# Sheet1.net
KiCad netlist of a schematic drawn in Altium Designer
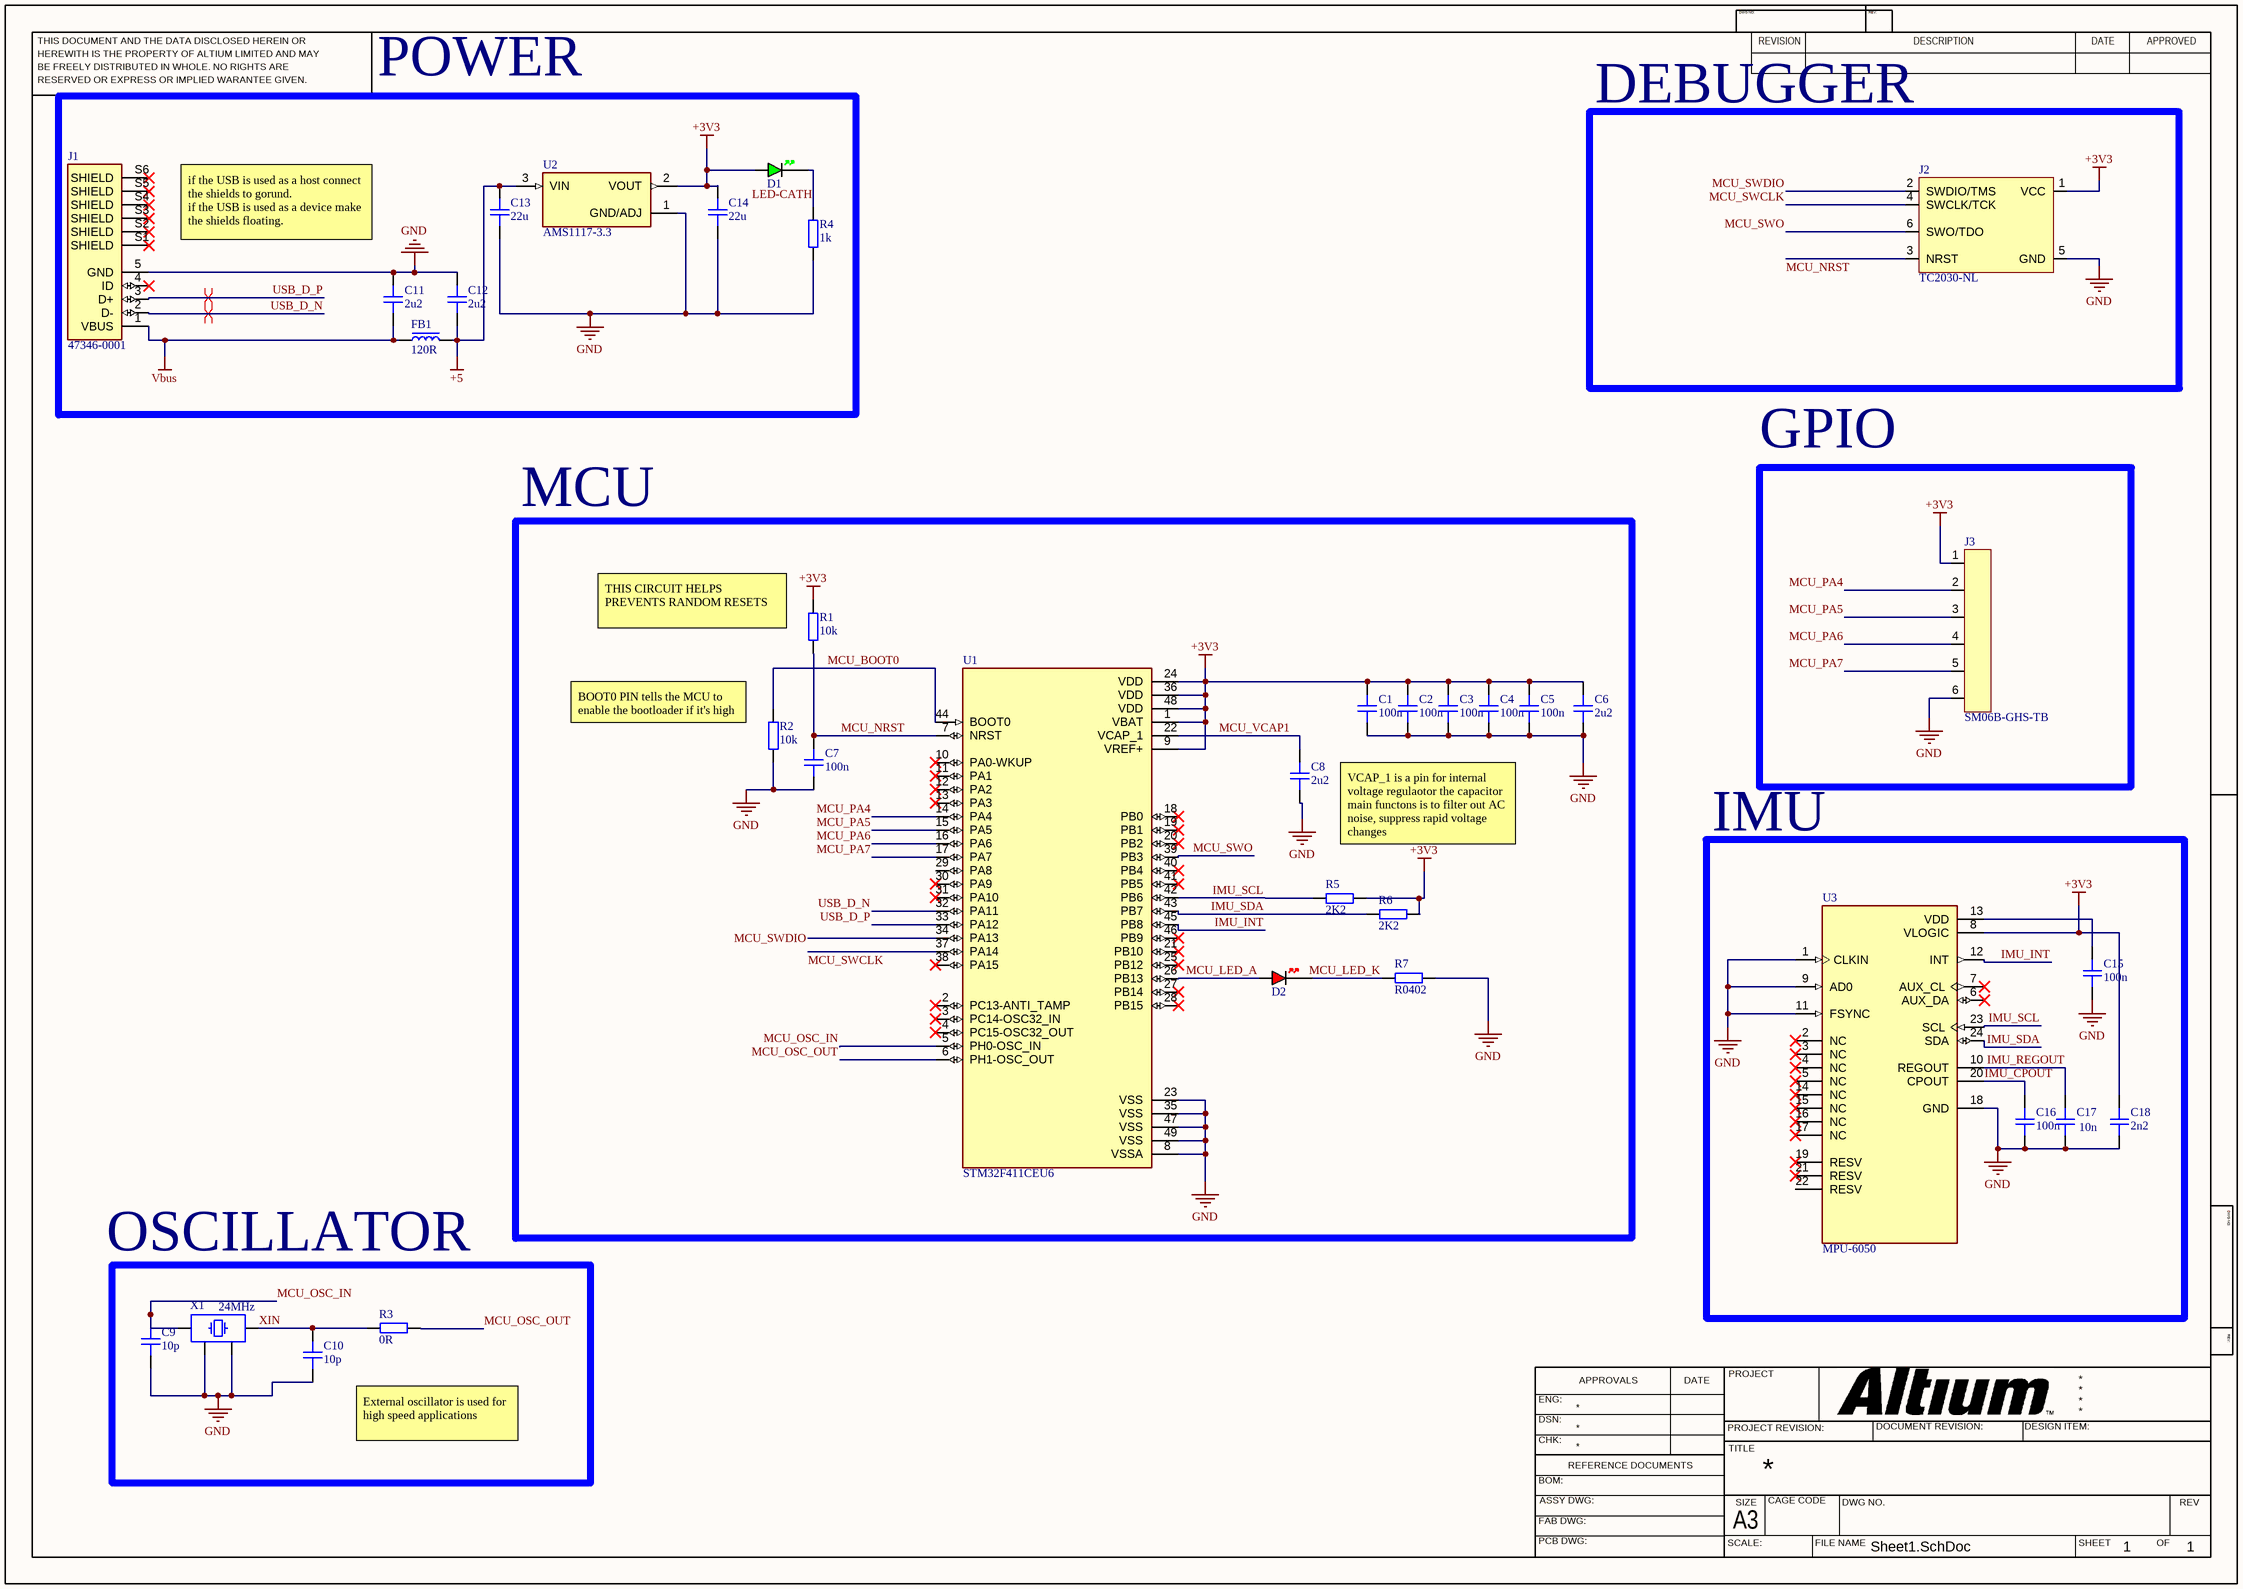
[diagram p0: Sheet1.SchDoc]

(export (version "E")
  (design (tool "Eeschema 10.0.6"))
  (components
    (comp (ref "C1")
      (value "100n")
      (footprint "CAP_0402")
      (description "Capacitor SMD 0402")
      (libsource (lib "Schematic-Lib-PhilsLab") (part "CAP_0402"))
    )
    (comp (ref "C2")
      (value "100n")
      (footprint "CAP_0402")
      (description "Capacitor SMD 0402")
      (libsource (lib "Schematic-Lib-PhilsLab") (part "CAP_0402"))
    )
    (comp (ref "C3")
      (value "100n")
      (footprint "CAP_0402")
      (description "Capacitor SMD 0402")
      (libsource (lib "Schematic-Lib-PhilsLab") (part "CAP_0402"))
    )
    (comp (ref "C4")
      (value "100n")
      (footprint "CAP_0402")
      (description "Capacitor SMD 0402")
      (libsource (lib "Schematic-Lib-PhilsLab") (part "CAP_0402"))
    )
    (comp (ref "C5")
      (value "100n")
      (footprint "CAP_0402")
      (description "Capacitor SMD 0402")
      (libsource (lib "Schematic-Lib-PhilsLab") (part "CAP_0402"))
    )
    (comp (ref "C6")
      (value "2u2")
      (footprint "CAP_0402")
      (description "Capacitor SMD 0402")
      (libsource (lib "Schematic-Lib-PhilsLab") (part "CAP_0402"))
    )
    (comp (ref "C7")
      (value "100n")
      (footprint "CAP_0402")
      (description "Capacitor SMD 0402")
      (libsource (lib "Schematic-Lib-PhilsLab") (part "CAP_0402"))
    )
    (comp (ref "C8")
      (value "2u2")
      (footprint "CAP_0402")
      (description "Capacitor SMD 0402")
      (libsource (lib "Schematic-Lib-PhilsLab") (part "CAP_0402"))
    )
    (comp (ref "C9")
      (value "10p")
      (footprint "CAP_0402")
      (description "Capacitor SMD 0402")
      (libsource (lib "Schematic-Lib-PhilsLab") (part "CAP_0402"))
    )
    (comp (ref "C10")
      (value "10p")
      (footprint "CAP_0402")
      (description "Capacitor SMD 0402")
      (libsource (lib "Schematic-Lib-PhilsLab") (part "CAP_0402"))
    )
    (comp (ref "C11")
      (value "2u2")
      (footprint "CAP_0402")
      (description "Capacitor SMD 0402")
      (libsource (lib "Schematic-Lib-PhilsLab") (part "CAP_0402"))
    )
    (comp (ref "C12")
      (value "2u2")
      (footprint "CAP_0402")
      (description "Capacitor SMD 0402")
      (libsource (lib "Schematic-Lib-PhilsLab") (part "CAP_0402"))
    )
    (comp (ref "C13")
      (value "22u")
      (footprint "CAP_0402")
      (description "Capacitor SMD 0402")
      (libsource (lib "Schematic-Lib-PhilsLab") (part "CAP_0402"))
    )
    (comp (ref "C14")
      (value "22u")
      (footprint "CAP_0402")
      (description "Capacitor SMD 0402")
      (libsource (lib "Schematic-Lib-PhilsLab") (part "CAP_0402"))
    )
    (comp (ref "C15")
      (value "100n")
      (footprint "CAP_0402")
      (description "Capacitor SMD 0402")
      (libsource (lib "Schematic-Lib-PhilsLab") (part "CAP_0402"))
    )
    (comp (ref "C16")
      (value "100n")
      (footprint "CAP_0402")
      (description "Capacitor SMD 0402")
      (libsource (lib "Schematic-Lib-PhilsLab") (part "CAP_0402"))
    )
    (comp (ref "C17")
      (value "10n")
      (footprint "CAP_0402")
      (description "Capacitor SMD 0402")
      (libsource (lib "Schematic-Lib-PhilsLab") (part "CAP_0402"))
    )
    (comp (ref "C18")
      (value "2n2")
      (footprint "CAP_0402")
      (description "Capacitor SMD 0402")
      (libsource (lib "Schematic-Lib-PhilsLab") (part "CAP_0402"))
    )
    (comp (ref "D1")
      (value "GREEN")
      (footprint "LED_0402_GREEN")
      (description "LED 0402 GREEN SMD")
      (libsource (lib "Schematic-Lib-PhilsLab") (part "LED_0402_GREEN"))
    )
    (comp (ref "D2")
      (value "RED")
      (footprint "LED_0402_RED")
      (description "LED 0402 RED SMD")
      (libsource (lib "Schematic-Lib-PhilsLab") (part "LED_0402_RED"))
    )
    (comp (ref "FB1")
      (value "120R")
      (footprint "FB_0805")
      (description "Ferrite Bead SMD 0805")
      (libsource (lib "Schematic-Lib-PhilsLab") (part "FB_0805"))
    )
    (comp (ref "J1")
      (value "47346-0001")
      (footprint "MOLEX_47346-0001")
      (description "Conn Data USB Micro B w/Flange SMT Bottom Mnt LF ¦ Molex Incorporated 47346-0001")
      (fields (field (name "MF") "Molex"))
      (libsource (lib "47346-0001") (part "47346-0001"))
    )
    (comp (ref "J2")
      (value "TC2030-NL")
      (footprint "TC2030-NL-FP")
      (description "Tag-Connect No-Solder SWD Debug Connector (No Legs) DO NOT PLACE")
      (fields
        (field (name "MANUFACTURER") "Tag-Connect")
        (field (name "MANUFACTURER PART NUMBER") "TC2030-NL-FP")
      )
      (libsource (lib "Schematic-Lib-PhilsLab") (part "TC2030-NL"))
    )
    (comp (ref "J3")
      (value "SM06B-GHS-TB")
      (footprint "SM06B-GHS-TB")
      (description "Header Connector 6 Position 1.25MM Pitch SMD Horizontal JST GH")
      (fields (field (name "MANUFACTURER") "JST"))
      (libsource (lib "Schematic-Lib-PhilsLab") (part "SM06B-GHS-TB"))
    )
    (comp (ref "R1")
      (value "10k")
      (footprint "RES_0402")
      (description "Resistor SMD 0402")
      (libsource (lib "Schematic-Lib-PhilsLab") (part "RES_0402"))
    )
    (comp (ref "R2")
      (value "10k")
      (footprint "RES_0402")
      (description "Resistor SMD 0402")
      (libsource (lib "Schematic-Lib-PhilsLab") (part "RES_0402"))
    )
    (comp (ref "R3")
      (value "0R")
      (footprint "RES_0402")
      (description "Resistor SMD 0402")
      (libsource (lib "Schematic-Lib-PhilsLab") (part "RES_0402"))
    )
    (comp (ref "R4")
      (value "1k")
      (footprint "RES_0402")
      (description "Resistor SMD 0402")
      (libsource (lib "Schematic-Lib-PhilsLab") (part "RES_0402"))
    )
    (comp (ref "R5")
      (value "2K2")
      (footprint "RES_0402")
      (description "Resistor SMD 0402")
      (libsource (lib "Schematic-Lib-PhilsLab") (part "RES_0402"))
    )
    (comp (ref "R6")
      (value "2K2")
      (footprint "RES_0402")
      (description "Resistor SMD 0402")
      (libsource (lib "Schematic-Lib-PhilsLab") (part "RES_0402"))
    )
    (comp (ref "R7")
      (value "R0402")
      (footprint "RES_0402")
      (description "Resistor SMD 0402")
      (libsource (lib "Schematic-Lib-PhilsLab") (part "RES_0402"))
    )
    (comp (ref "U1")
      (value "STM32F411CEU6")
      (footprint "QFN50P700X700X60-49N")
      (libsource (lib "STM32F411CEU6") (part "STM32F411CEU6"))
    )
    (comp (ref "U2")
      (value "AMS1117-3.3")
      (footprint "SOT229P700X180-4N")
      (description "Sot223/Pkg 1-Amp 3.3-Volt Low Drop Out Voltage Regulatator")
      (fields (field (name "MF") "Advanced Monolithic Systems"))
      (libsource (lib "AMS1117-3.3") (part "AMS1117-3.3"))
    )
    (comp (ref "U3")
      (value "MPU-6050")
      (footprint "QFN50P400X400X95-24N")
      (description "MPU-6050 series Accelerometer, Gyroscope, 3 Axis Sensor Evaluation Board")
      (fields (field (name "MF") "TDK InvenSense"))
      (libsource (lib "MPU-6050") (part "MPU-6050"))
    )
    (comp (ref "X1")
      (value "24MHz")
      (footprint "XTAL_3225")
      (description "Crystal SMD 24MHz 10PPM 7pF 3225")
      (fields
        (field (name "MANUFACTURER") "Epson")
        (field (name "MANUFACTURER PART NUMBER") "TSX-3225 24.0000MF15X-AC")
      )
      (libsource (lib "Schematic-Lib-PhilsLab") (part "TSX-3225_24.0000MF15X-AC"))
    )
  )
  (nets
    (net (code "1") (name "+3V3") (class "Default")
      (node (ref "C1") (pin "2") (pinfunction "2_2") (pintype "passive"))
      (node (ref "C14") (pin "2") (pinfunction "2_2") (pintype "passive"))
      (node (ref "C18") (pin "2") (pinfunction "2_2") (pintype "passive"))
      (node (ref "C2") (pin "2") (pinfunction "2_2") (pintype "passive"))
      (node (ref "C3") (pin "2") (pinfunction "2_2") (pintype "passive"))
      (node (ref "C4") (pin "2") (pinfunction "2_2") (pintype "passive"))
      (node (ref "C5") (pin "2") (pinfunction "2_2") (pintype "passive"))
      (node (ref "C6") (pin "2") (pinfunction "2_2") (pintype "passive"))
      (node (ref "D1") (pin "A") (pinfunction "A_A") (pintype "passive"))
      (node (ref "J2") (pin "1") (pinfunction "VCC_1") (pintype "passive"))
      (node (ref "J3") (pin "1") (pinfunction "1_1") (pintype "passive"))
      (node (ref "R1") (pin "2") (pinfunction "2_2") (pintype "passive"))
      (node (ref "R5") (pin "2") (pinfunction "2_2") (pintype "passive"))
      (node (ref "R6") (pin "2") (pinfunction "2_2") (pintype "passive"))
      (node (ref "U1") (pin "1") (pinfunction "VBAT_1") (pintype "power_in"))
      (node (ref "U1") (pin "24") (pinfunction "VDD_24") (pintype "power_in"))
      (node (ref "U1") (pin "36") (pinfunction "VDD_36") (pintype "power_in"))
      (node (ref "U1") (pin "48") (pinfunction "VDD_48") (pintype "power_in"))
      (node (ref "U1") (pin "9") (pinfunction "VREF+_9") (pintype "power_in"))
      (node (ref "U2") (pin "2") (pinfunction "VOUT_2") (pintype "output"))
      (node (ref "U3") (pin "8") (pinfunction "VLOGIC_8") (pintype "power_in"))
    )
    (net (code "2") (name "+5") (class "Default")
      (node (ref "C12") (pin "1") (pinfunction "1_1") (pintype "passive"))
      (node (ref "C13") (pin "2") (pinfunction "2_2") (pintype "passive"))
      (node (ref "FB1") (pin "2") (pinfunction "2_2") (pintype "passive"))
      (node (ref "U2") (pin "3") (pinfunction "VIN_3") (pintype "input"))
    )
    (net (code "3") (name "/IMU_CPOUT") (class "Default")
      (node (ref "C16") (pin "2") (pinfunction "2_2") (pintype "passive"))
      (node (ref "U3") (pin "20") (pinfunction "CPOUT_20") (pintype "passive"))
    )
    (net (code "4") (name "/IMU_INT") (class "Default")
      (node (ref "U1") (pin "45") (pinfunction "PB8_45") (pintype "bidirectional"))
      (node (ref "U3") (pin "12") (pinfunction "INT_12") (pintype "output"))
    )
    (net (code "5") (name "/IMU_REGOUT") (class "Default")
      (node (ref "C17") (pin "2") (pinfunction "2_2") (pintype "passive"))
      (node (ref "U3") (pin "10") (pinfunction "REGOUT_10") (pintype "passive"))
    )
    (net (code "6") (name "/IMU_SCL") (class "Default")
      (node (ref "R5") (pin "1") (pinfunction "1_1") (pintype "passive"))
      (node (ref "U1") (pin "42") (pinfunction "PB6_42") (pintype "bidirectional"))
      (node (ref "U3") (pin "23") (pinfunction "SCL_23") (pintype "input"))
    )
    (net (code "7") (name "/IMU_SDA") (class "Default")
      (node (ref "R6") (pin "1") (pinfunction "1_1") (pintype "passive"))
      (node (ref "U1") (pin "43") (pinfunction "PB7_43") (pintype "bidirectional"))
      (node (ref "U3") (pin "24") (pinfunction "SDA_24") (pintype "bidirectional"))
    )
    (net (code "8") (name "/LED-CATH") (class "Default")
      (node (ref "D1") (pin "K") (pinfunction "K_K") (pintype "passive"))
      (node (ref "R4") (pin "2") (pinfunction "2_2") (pintype "passive"))
    )
    (net (code "9") (name "/MCU_BOOT0") (class "Default")
      (node (ref "R2") (pin "2") (pinfunction "2_2") (pintype "passive"))
      (node (ref "U1") (pin "44") (pinfunction "BOOT0_44") (pintype "input"))
    )
    (net (code "10") (name "/MCU_LED_A") (class "Default")
      (node (ref "D2") (pin "A") (pinfunction "A_A") (pintype "passive"))
      (node (ref "U1") (pin "26") (pinfunction "PB13_26") (pintype "bidirectional"))
    )
    (net (code "11") (name "/MCU_LED_K") (class "Default")
      (node (ref "D2") (pin "K") (pinfunction "K_K") (pintype "passive"))
      (node (ref "R7") (pin "1") (pinfunction "1_1") (pintype "passive"))
    )
    (net (code "12") (name "/MCU_NRST") (class "Default")
      (node (ref "C7") (pin "2") (pinfunction "2_2") (pintype "passive"))
      (node (ref "J2") (pin "3") (pinfunction "NRST_3") (pintype "passive"))
      (node (ref "R1") (pin "1") (pinfunction "1_1") (pintype "passive"))
      (node (ref "U1") (pin "7") (pinfunction "NRST_7") (pintype "bidirectional"))
    )
    (net (code "13") (name "/MCU_OSC_IN") (class "Default")
      (node (ref "C9") (pin "2") (pinfunction "2_2") (pintype "passive"))
      (node (ref "U1") (pin "5") (pinfunction "PH0-OSC_IN_5") (pintype "bidirectional"))
      (node (ref "X1") (pin "1") (pinfunction "1_1") (pintype "passive"))
    )
    (net (code "14") (name "/MCU_OSC_OUT") (class "Default")
      (node (ref "R3") (pin "2") (pinfunction "2_2") (pintype "passive"))
      (node (ref "U1") (pin "6") (pinfunction "PH1-OSC_OUT_6") (pintype "bidirectional"))
    )
    (net (code "15") (name "/MCU_PA4") (class "Default")
      (node (ref "J3") (pin "2") (pinfunction "2_2") (pintype "passive"))
      (node (ref "U1") (pin "14") (pinfunction "PA4_14") (pintype "bidirectional"))
    )
    (net (code "16") (name "/MCU_PA5") (class "Default")
      (node (ref "J3") (pin "3") (pinfunction "3_3") (pintype "passive"))
      (node (ref "U1") (pin "15") (pinfunction "PA5_15") (pintype "bidirectional"))
    )
    (net (code "17") (name "/MCU_PA6") (class "Default")
      (node (ref "J3") (pin "4") (pinfunction "4_4") (pintype "passive"))
      (node (ref "U1") (pin "16") (pinfunction "PA6_16") (pintype "bidirectional"))
    )
    (net (code "18") (name "/MCU_PA7") (class "Default")
      (node (ref "J3") (pin "5") (pinfunction "5_5") (pintype "passive"))
      (node (ref "U1") (pin "17") (pinfunction "PA7_17") (pintype "bidirectional"))
    )
    (net (code "19") (name "/MCU_SWCLK") (class "Default")
      (node (ref "J2") (pin "4") (pinfunction "SWCLK/TCK_4") (pintype "passive"))
      (node (ref "U1") (pin "37") (pinfunction "PA14_37") (pintype "bidirectional"))
    )
    (net (code "20") (name "/MCU_SWDIO") (class "Default")
      (node (ref "J2") (pin "2") (pinfunction "SWDIO/TMS_2") (pintype "passive"))
      (node (ref "U1") (pin "34") (pinfunction "PA13_34") (pintype "bidirectional"))
    )
    (net (code "21") (name "/MCU_SWO") (class "Default")
      (node (ref "J2") (pin "6") (pinfunction "SWO/TDO_6") (pintype "passive"))
      (node (ref "U1") (pin "39") (pinfunction "PB3_39") (pintype "bidirectional"))
    )
    (net (code "22") (name "/MCU_VCAP1") (class "Default")
      (node (ref "C8") (pin "2") (pinfunction "2_2") (pintype "passive"))
      (node (ref "U1") (pin "22") (pinfunction "VCAP_1_22") (pintype "power_in"))
    )
    (net (code "23") (name "/USB_D_N") (class "Default")
      (node (ref "J1") (pin "2") (pinfunction "D-_2") (pintype "bidirectional"))
      (node (ref "U1") (pin "32") (pinfunction "PA11_32") (pintype "bidirectional"))
    )
    (net (code "24") (name "/USB_D_P") (class "Default")
      (node (ref "J1") (pin "3") (pinfunction "D+_3") (pintype "bidirectional"))
      (node (ref "U1") (pin "33") (pinfunction "PA12_33") (pintype "bidirectional"))
    )
    (net (code "25") (name "/XIN") (class "Default")
      (node (ref "C10") (pin "2") (pinfunction "2_2") (pintype "passive"))
      (node (ref "R3") (pin "1") (pinfunction "1_1") (pintype "passive"))
      (node (ref "X1") (pin "3") (pinfunction "3_3") (pintype "passive"))
    )
    (net (code "26") (name "GND") (class "Default")
      (node (ref "C1") (pin "1") (pinfunction "1_1") (pintype "passive"))
      (node (ref "C10") (pin "1") (pinfunction "1_1") (pintype "passive"))
      (node (ref "C11") (pin "2") (pinfunction "2_2") (pintype "passive"))
      (node (ref "C12") (pin "2") (pinfunction "2_2") (pintype "passive"))
      (node (ref "C13") (pin "1") (pinfunction "1_1") (pintype "passive"))
      (node (ref "C14") (pin "1") (pinfunction "1_1") (pintype "passive"))
      (node (ref "C15") (pin "1") (pinfunction "1_1") (pintype "passive"))
      (node (ref "C16") (pin "1") (pinfunction "1_1") (pintype "passive"))
      (node (ref "C17") (pin "1") (pinfunction "1_1") (pintype "passive"))
      (node (ref "C18") (pin "1") (pinfunction "1_1") (pintype "passive"))
      (node (ref "C2") (pin "1") (pinfunction "1_1") (pintype "passive"))
      (node (ref "C3") (pin "1") (pinfunction "1_1") (pintype "passive"))
      (node (ref "C4") (pin "1") (pinfunction "1_1") (pintype "passive"))
      (node (ref "C5") (pin "1") (pinfunction "1_1") (pintype "passive"))
      (node (ref "C6") (pin "1") (pinfunction "1_1") (pintype "passive"))
      (node (ref "C7") (pin "1") (pinfunction "1_1") (pintype "passive"))
      (node (ref "C8") (pin "1") (pinfunction "1_1") (pintype "passive"))
      (node (ref "C9") (pin "1") (pinfunction "1_1") (pintype "passive"))
      (node (ref "J1") (pin "5") (pinfunction "GND_5") (pintype "power_in"))
      (node (ref "J2") (pin "5") (pinfunction "GND_5") (pintype "passive"))
      (node (ref "J3") (pin "6") (pinfunction "6_6") (pintype "passive"))
      (node (ref "R2") (pin "1") (pinfunction "1_1") (pintype "passive"))
      (node (ref "R4") (pin "1") (pinfunction "1_1") (pintype "passive"))
      (node (ref "R7") (pin "2") (pinfunction "2_2") (pintype "passive"))
      (node (ref "U1") (pin "23") (pinfunction "VSS_23") (pintype "power_in"))
      (node (ref "U1") (pin "35") (pinfunction "VSS_35") (pintype "power_in"))
      (node (ref "U1") (pin "47") (pinfunction "VSS_47") (pintype "power_in"))
      (node (ref "U1") (pin "49") (pinfunction "VSS_49") (pintype "power_in"))
      (node (ref "U1") (pin "8") (pinfunction "VSSA_8") (pintype "power_in"))
      (node (ref "U2") (pin "1") (pinfunction "GND/ADJ_1") (pintype "power_in"))
      (node (ref "U3") (pin "1") (pinfunction "CLKIN_1") (pintype "input"))
      (node (ref "U3") (pin "11") (pinfunction "FSYNC_11") (pintype "input"))
      (node (ref "U3") (pin "18") (pinfunction "GND_18") (pintype "power_in"))
      (node (ref "U3") (pin "9") (pinfunction "AD0_9") (pintype "input"))
      (node (ref "X1") (pin "2") (pinfunction "2_2") (pintype "passive"))
      (node (ref "X1") (pin "4") (pinfunction "4_4") (pintype "passive"))
    )
    (net (code "27") (name "Net-(U3-VDD)") (class "Default")
      (node (ref "C15") (pin "2") (pinfunction "2_2") (pintype "passive"))
      (node (ref "U3") (pin "13") (pinfunction "VDD_13") (pintype "power_in"))
    )
    (net (code "28") (name "Vbus") (class "Default")
      (node (ref "C11") (pin "1") (pinfunction "1_1") (pintype "passive"))
      (node (ref "FB1") (pin "1") (pinfunction "1_1") (pintype "passive"))
      (node (ref "J1") (pin "1") (pinfunction "VBUS_1") (pintype "power_in"))
    )
    (net (code "29") (name "unconnected-(J1-ID-Pad4)") (class "Default")
      (node (ref "J1") (pin "4") (pinfunction "ID_4") (pintype "bidirectional+no_connect"))
    )
    (net (code "30") (name "unconnected-(J1-SHIELD-PadS1)") (class "Default")
      (node (ref "J1") (pin "S1") (pinfunction "SHIELD_S1") (pintype "passive+no_connect"))
    )
    (net (code "31") (name "unconnected-(J1-SHIELD-PadS2)") (class "Default")
      (node (ref "J1") (pin "S2") (pinfunction "SHIELD_S2") (pintype "passive+no_connect"))
    )
    (net (code "32") (name "unconnected-(J1-SHIELD-PadS3)") (class "Default")
      (node (ref "J1") (pin "S3") (pinfunction "SHIELD_S3") (pintype "passive+no_connect"))
    )
    (net (code "33") (name "unconnected-(J1-SHIELD-PadS4)") (class "Default")
      (node (ref "J1") (pin "S4") (pinfunction "SHIELD_S4") (pintype "passive+no_connect"))
    )
    (net (code "34") (name "unconnected-(J1-SHIELD-PadS5)") (class "Default")
      (node (ref "J1") (pin "S5") (pinfunction "SHIELD_S5") (pintype "passive+no_connect"))
    )
    (net (code "35") (name "unconnected-(J1-SHIELD-PadS6)") (class "Default")
      (node (ref "J1") (pin "S6") (pinfunction "SHIELD_S6") (pintype "passive+no_connect"))
    )
    (net (code "36") (name "unconnected-(U1-PA0-WKUP-Pad10)") (class "Default")
      (node (ref "U1") (pin "10") (pinfunction "PA0-WKUP_10") (pintype "bidirectional+no_connect"))
    )
    (net (code "37") (name "unconnected-(U1-PA1-Pad11)") (class "Default")
      (node (ref "U1") (pin "11") (pinfunction "PA1_11") (pintype "bidirectional+no_connect"))
    )
    (net (code "38") (name "unconnected-(U1-PA2-Pad12)") (class "Default")
      (node (ref "U1") (pin "12") (pinfunction "PA2_12") (pintype "bidirectional+no_connect"))
    )
    (net (code "39") (name "unconnected-(U1-PA3-Pad13)") (class "Default")
      (node (ref "U1") (pin "13") (pinfunction "PA3_13") (pintype "bidirectional+no_connect"))
    )
    (net (code "40") (name "unconnected-(U1-PA8-Pad29)") (class "Default")
      (node (ref "U1") (pin "29") (pinfunction "PA8_29") (pintype "bidirectional"))
    )
    (net (code "41") (name "unconnected-(U1-PA9-Pad30)") (class "Default")
      (node (ref "U1") (pin "30") (pinfunction "PA9_30") (pintype "bidirectional+no_connect"))
    )
    (net (code "42") (name "unconnected-(U1-PA10-Pad31)") (class "Default")
      (node (ref "U1") (pin "31") (pinfunction "PA10_31") (pintype "bidirectional+no_connect"))
    )
    (net (code "43") (name "unconnected-(U1-PA15-Pad38)") (class "Default")
      (node (ref "U1") (pin "38") (pinfunction "PA15_38") (pintype "bidirectional+no_connect"))
    )
    (net (code "44") (name "unconnected-(U1-PB0-Pad18)") (class "Default")
      (node (ref "U1") (pin "18") (pinfunction "PB0_18") (pintype "bidirectional+no_connect"))
    )
    (net (code "45") (name "unconnected-(U1-PB1-Pad19)") (class "Default")
      (node (ref "U1") (pin "19") (pinfunction "PB1_19") (pintype "bidirectional+no_connect"))
    )
    (net (code "46") (name "unconnected-(U1-PB2-Pad20)") (class "Default")
      (node (ref "U1") (pin "20") (pinfunction "PB2_20") (pintype "bidirectional+no_connect"))
    )
    (net (code "47") (name "unconnected-(U1-PB4-Pad40)") (class "Default")
      (node (ref "U1") (pin "40") (pinfunction "PB4_40") (pintype "bidirectional+no_connect"))
    )
    (net (code "48") (name "unconnected-(U1-PB5-Pad41)") (class "Default")
      (node (ref "U1") (pin "41") (pinfunction "PB5_41") (pintype "bidirectional+no_connect"))
    )
    (net (code "49") (name "unconnected-(U1-PB9-Pad46)") (class "Default")
      (node (ref "U1") (pin "46") (pinfunction "PB9_46") (pintype "bidirectional+no_connect"))
    )
    (net (code "50") (name "unconnected-(U1-PB10-Pad21)") (class "Default")
      (node (ref "U1") (pin "21") (pinfunction "PB10_21") (pintype "bidirectional+no_connect"))
    )
    (net (code "51") (name "unconnected-(U1-PB12-Pad25)") (class "Default")
      (node (ref "U1") (pin "25") (pinfunction "PB12_25") (pintype "bidirectional+no_connect"))
    )
    (net (code "52") (name "unconnected-(U1-PB14-Pad27)") (class "Default")
      (node (ref "U1") (pin "27") (pinfunction "PB14_27") (pintype "bidirectional+no_connect"))
    )
    (net (code "53") (name "unconnected-(U1-PB15-Pad28)") (class "Default")
      (node (ref "U1") (pin "28") (pinfunction "PB15_28") (pintype "bidirectional+no_connect"))
    )
    (net (code "54") (name "unconnected-(U1-PC13-ANTI_TAMP-Pad2)") (class "Default")
      (node (ref "U1") (pin "2") (pinfunction "PC13-ANTI_TAMP_2") (pintype "bidirectional+no_connect"))
    )
    (net (code "55") (name "unconnected-(U1-PC14-OSC32_IN-Pad3)") (class "Default")
      (node (ref "U1") (pin "3") (pinfunction "PC14-OSC32_IN_3") (pintype "bidirectional+no_connect"))
    )
    (net (code "56") (name "unconnected-(U1-PC15-OSC32_OUT-Pad4)") (class "Default")
      (node (ref "U1") (pin "4") (pinfunction "PC15-OSC32_OUT_4") (pintype "bidirectional+no_connect"))
    )
    (net (code "57") (name "unconnected-(U3-AUX_CL-Pad7)") (class "Default")
      (node (ref "U3") (pin "7") (pinfunction "AUX_CL_7") (pintype "output+no_connect"))
    )
    (net (code "58") (name "unconnected-(U3-AUX_DA-Pad6)") (class "Default")
      (node (ref "U3") (pin "6") (pinfunction "AUX_DA_6") (pintype "bidirectional+no_connect"))
    )
    (net (code "59") (name "unconnected-(U3-NC-Pad2)") (class "Default")
      (node (ref "U3") (pin "2") (pinfunction "NC_2") (pintype "passive+no_connect"))
    )
    (net (code "60") (name "unconnected-(U3-NC-Pad3)") (class "Default")
      (node (ref "U3") (pin "3") (pinfunction "NC_3") (pintype "passive+no_connect"))
    )
    (net (code "61") (name "unconnected-(U3-NC-Pad4)") (class "Default")
      (node (ref "U3") (pin "4") (pinfunction "NC_4") (pintype "passive+no_connect"))
    )
    (net (code "62") (name "unconnected-(U3-NC-Pad5)") (class "Default")
      (node (ref "U3") (pin "5") (pinfunction "NC_5") (pintype "passive+no_connect"))
    )
    (net (code "63") (name "unconnected-(U3-NC-Pad14)") (class "Default")
      (node (ref "U3") (pin "14") (pinfunction "NC_14") (pintype "passive+no_connect"))
    )
    (net (code "64") (name "unconnected-(U3-NC-Pad15)") (class "Default")
      (node (ref "U3") (pin "15") (pinfunction "NC_15") (pintype "passive+no_connect"))
    )
    (net (code "65") (name "unconnected-(U3-NC-Pad16)") (class "Default")
      (node (ref "U3") (pin "16") (pinfunction "NC_16") (pintype "passive+no_connect"))
    )
    (net (code "66") (name "unconnected-(U3-NC-Pad17)") (class "Default")
      (node (ref "U3") (pin "17") (pinfunction "NC_17") (pintype "passive+no_connect"))
    )
    (net (code "67") (name "unconnected-(U3-RESV-Pad19)") (class "Default")
      (node (ref "U3") (pin "19") (pinfunction "RESV_19") (pintype "passive+no_connect"))
    )
    (net (code "68") (name "unconnected-(U3-RESV-Pad21)") (class "Default")
      (node (ref "U3") (pin "21") (pinfunction "RESV_21") (pintype "passive+no_connect"))
    )
    (net (code "69") (name "unconnected-(U3-RESV-Pad22)") (class "Default")
      (node (ref "U3") (pin "22") (pinfunction "RESV_22") (pintype "passive"))
    )
  )
)
